# laser_diode_driver.net
KiCad netlist of a schematic drawn in EAGLE
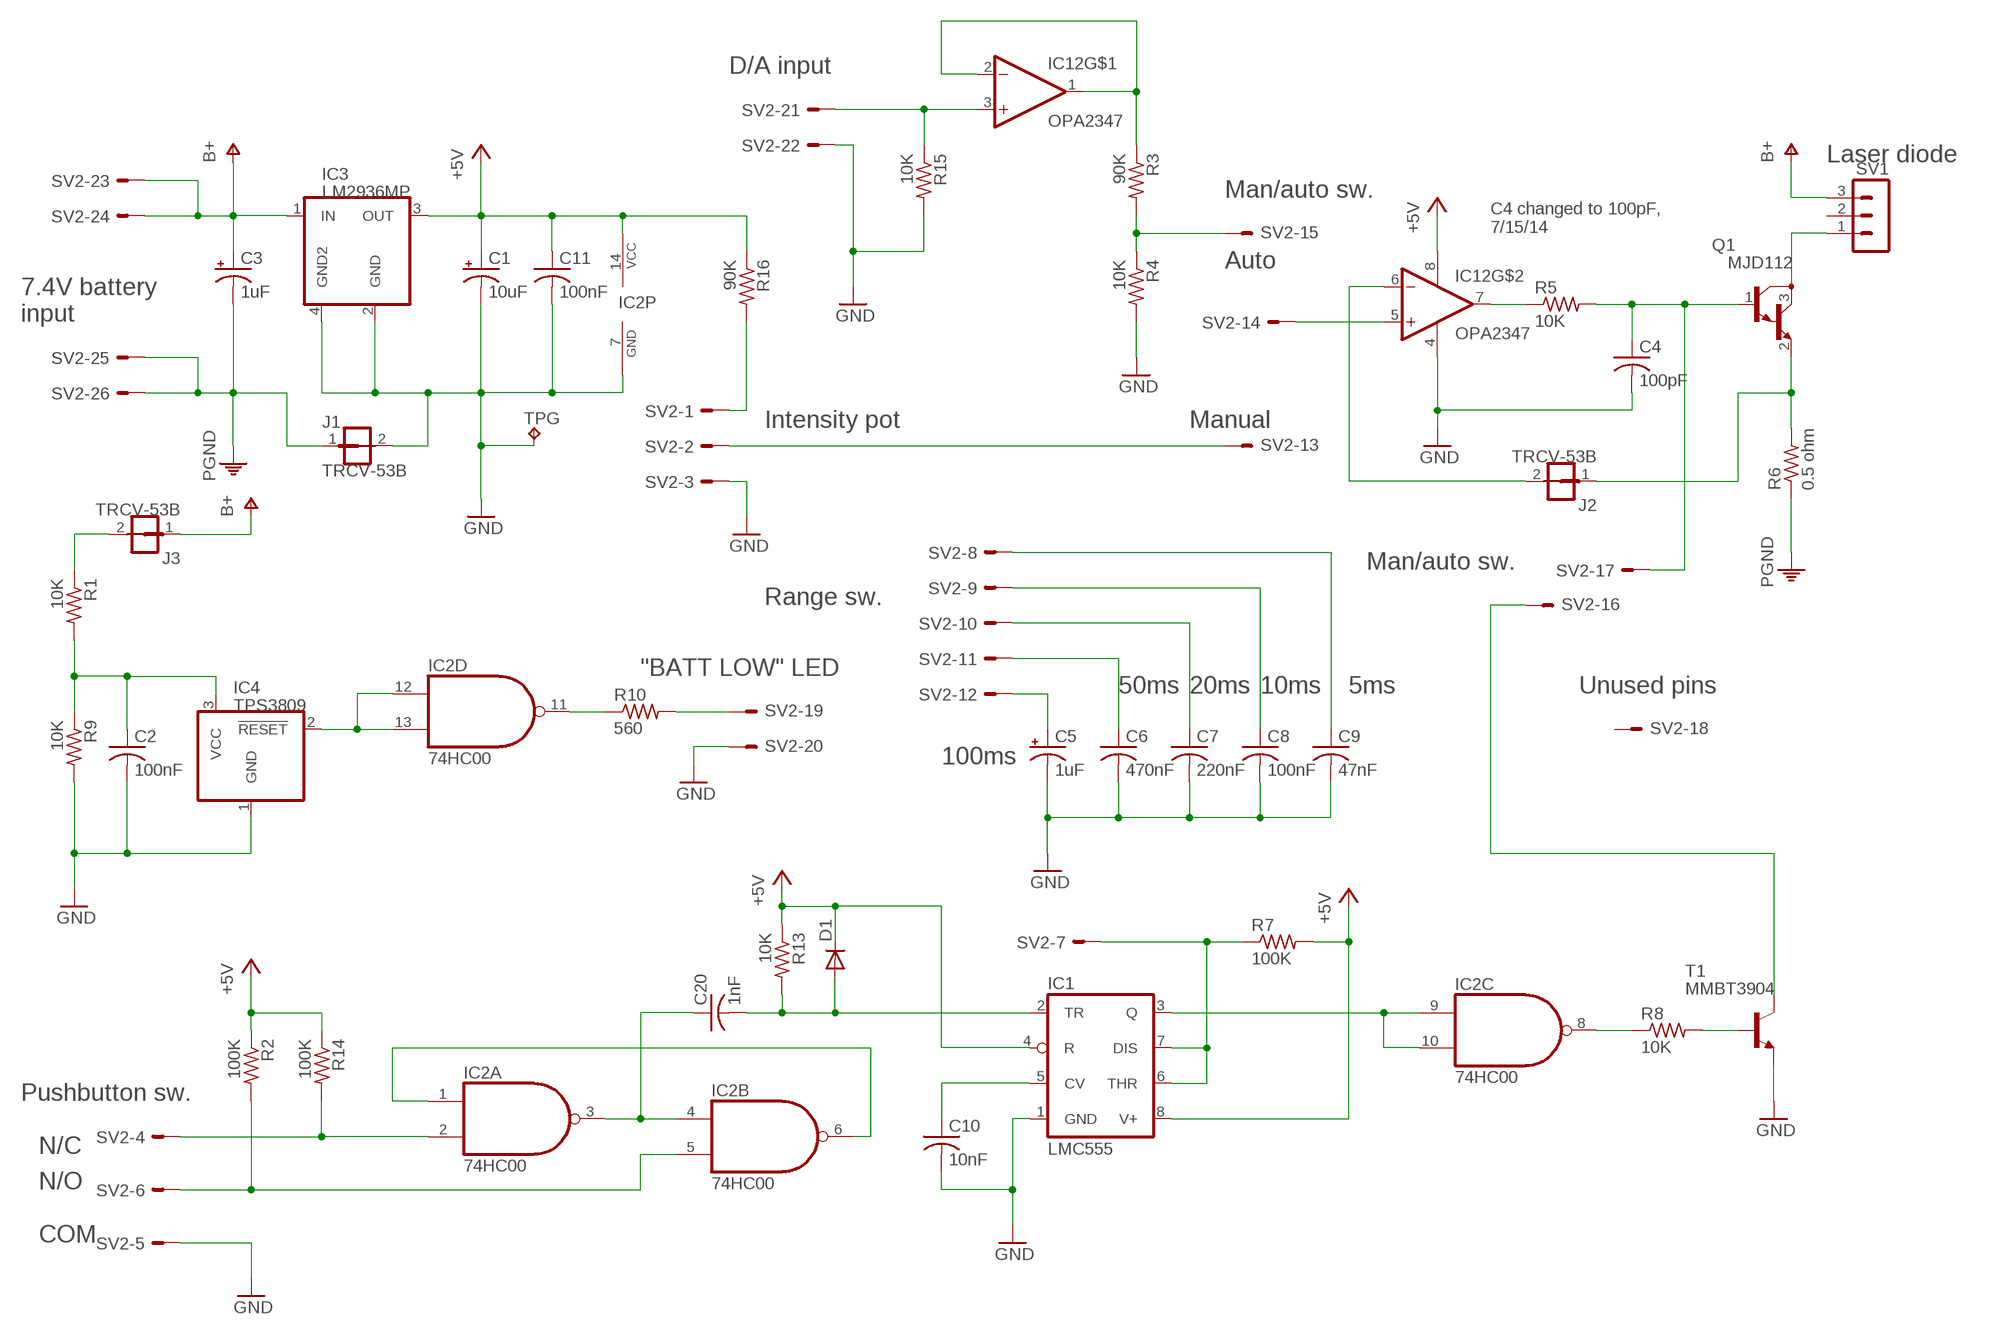
[diagram p0: schematic, sheet 1]

(export (version "E")
  (design (tool "Eeschema 10.0.6"))
  (components
    (comp (ref "C1")
      (value "10uF")
      (footprint "eagle-import:SMC_B")
      (libsource (lib "eagle-import") (part "CPOL-USSMCB"))
    )
    (comp (ref "C2")
      (value "100nF")
      (footprint "eagle-import:C0805")
      (libsource (lib "eagle-import") (part "C-USC0805"))
    )
    (comp (ref "C3")
      (value "1uF")
      (footprint "eagle-import:SMC_B")
      (libsource (lib "eagle-import") (part "CPOL-USSMCB"))
    )
    (comp (ref "C4")
      (value "100pF")
      (footprint "eagle-import:C0805")
      (libsource (lib "eagle-import") (part "C-USC0805"))
    )
    (comp (ref "C5")
      (value "1uF")
      (footprint "eagle-import:SMC_B")
      (libsource (lib "eagle-import") (part "CPOL-USSMCB"))
    )
    (comp (ref "C6")
      (value "470nF")
      (footprint "eagle-import:C0805")
      (libsource (lib "eagle-import") (part "C-USC0805"))
    )
    (comp (ref "C7")
      (value "220nF")
      (footprint "eagle-import:C0805")
      (libsource (lib "eagle-import") (part "C-USC0805"))
    )
    (comp (ref "C8")
      (value "100nF")
      (footprint "eagle-import:C0805")
      (libsource (lib "eagle-import") (part "C-USC0805"))
    )
    (comp (ref "C9")
      (value "47nF")
      (footprint "eagle-import:C0805")
      (libsource (lib "eagle-import") (part "C-USC0805"))
    )
    (comp (ref "C10")
      (value "10nF")
      (footprint "eagle-import:C0805")
      (libsource (lib "eagle-import") (part "C-USC0805"))
    )
    (comp (ref "C11")
      (value "100nF")
      (footprint "eagle-import:C0805")
      (libsource (lib "eagle-import") (part "C-USC0805"))
    )
    (comp (ref "C20")
      (value "1nF")
      (footprint "eagle-import:C0805")
      (libsource (lib "eagle-import") (part "C-USC0805"))
    )
    (comp (ref "D1")
      (value "DIODE-SOD123")
      (footprint "eagle-import:SOD123")
      (libsource (lib "eagle-import") (part "DIODE-SOD123"))
    )
    (comp (ref "IC1")
      (value "LMC555")
      (footprint "eagle-import:SO08")
      (libsource (lib "eagle-import") (part "555DLM"))
    )
    (comp (ref "IC2")
      (value "74HC00")
      (footprint "eagle-import:SO14")
      (libsource (lib "eagle-import") (part "7400DALS"))
    )
    (comp (ref "IC3")
      (value "LM2936MP")
      (footprint "eagle-import:SOT223")
      (libsource (lib "eagle-import") (part "LM2936MP"))
    )
    (comp (ref "IC4")
      (value "TPS3809")
      (footprint "eagle-import:SOT23")
      (libsource (lib "eagle-import") (part "TPS3809"))
    )
    (comp (ref "IC12")
      (value "OPA2347")
      (footprint "eagle-import:SO08")
      (libsource (lib "eagle-import") (part "OPA2227-SO8"))
    )
    (comp (ref "J1")
      (value "TRCV-53B")
      (footprint "eagle-import:JUMPER-TRACE-CONVERT-53-VER2")
      (libsource (lib "eagle-import") (part "TRCV-53B"))
    )
    (comp (ref "J2")
      (value "TRCV-53B")
      (footprint "eagle-import:JUMPER-TRACE-CONVERT-53-VER2")
      (libsource (lib "eagle-import") (part "TRCV-53B"))
    )
    (comp (ref "J3")
      (value "TRCV-53B")
      (footprint "eagle-import:JUMPER-TRACE-CONVERT-53-VER2")
      (libsource (lib "eagle-import") (part "TRCV-53B"))
    )
    (comp (ref "Q1")
      (value "MJD112")
      (footprint "eagle-import:TO252")
      (libsource (lib "eagle-import") (part "MJD112"))
    )
    (comp (ref "R1")
      (value "10K")
      (footprint "eagle-import:R0805")
      (libsource (lib "eagle-import") (part "R-US_R0805"))
    )
    (comp (ref "R2")
      (value "100K")
      (footprint "eagle-import:R0805")
      (libsource (lib "eagle-import") (part "R-US_R0805"))
    )
    (comp (ref "R3")
      (value "90K")
      (footprint "eagle-import:R0805")
      (libsource (lib "eagle-import") (part "R-US_R0805"))
    )
    (comp (ref "R4")
      (value "10K")
      (footprint "eagle-import:R0805")
      (libsource (lib "eagle-import") (part "R-US_R0805"))
    )
    (comp (ref "R5")
      (value "10K")
      (footprint "eagle-import:R0805")
      (libsource (lib "eagle-import") (part "R-US_R0805"))
    )
    (comp (ref "R6")
      (value "0.5 ohm")
      (footprint "eagle-import:R2512")
      (libsource (lib "eagle-import") (part "R-US_R2512"))
    )
    (comp (ref "R7")
      (value "100K")
      (footprint "eagle-import:R0805")
      (libsource (lib "eagle-import") (part "R-US_R0805"))
    )
    (comp (ref "R8")
      (value "10K")
      (footprint "eagle-import:R0805")
      (libsource (lib "eagle-import") (part "R-US_R0805"))
    )
    (comp (ref "R9")
      (value "10K")
      (footprint "eagle-import:R0805")
      (libsource (lib "eagle-import") (part "R-US_R0805"))
    )
    (comp (ref "R10")
      (value "560")
      (footprint "eagle-import:R0805")
      (libsource (lib "eagle-import") (part "R-US_R0805"))
    )
    (comp (ref "R13")
      (value "10K")
      (footprint "eagle-import:R0805")
      (libsource (lib "eagle-import") (part "R-US_R0805"))
    )
    (comp (ref "R14")
      (value "100K")
      (footprint "eagle-import:R0805")
      (libsource (lib "eagle-import") (part "R-US_R0805"))
    )
    (comp (ref "R15")
      (value "10K")
      (footprint "eagle-import:R0805")
      (libsource (lib "eagle-import") (part "R-US_R0805"))
    )
    (comp (ref "R16")
      (value "90K")
      (footprint "eagle-import:R0805")
      (libsource (lib "eagle-import") (part "R-US_R0805"))
    )
    (comp (ref "SV1")
      (value "MA03-1")
      (footprint "eagle-import:MA03-1")
      (libsource (lib "eagle-import") (part "MA03-1"))
    )
    (comp (ref "SV2")
      (value "ML26LE")
      (footprint "eagle-import:ML26L")
      (libsource (lib "eagle-import") (part "ML26?EL"))
    )
    (comp (ref "T1")
      (value "MMBT3904")
      (footprint "eagle-import:SOT23-BEC")
      (libsource (lib "eagle-import") (part "-NPN-SOT23-BECMMBT3904LT1"))
    )
    (comp (ref "TPG")
      (value "TP-040-100")
      (footprint "eagle-import:P1-040-100")
      (libsource (lib "eagle-import") (part "TP-040-100"))
    )
  )
  (nets
    (net (code "1") (name "+5V") (class "Default")
      (node (ref "C1") (pin "+") (pinfunction "+_+") (pintype "passive"))
      (node (ref "C11") (pin "1") (pinfunction "1_1") (pintype "passive"))
      (node (ref "D1") (pin "C") (pinfunction "C_C") (pintype "passive"))
      (node (ref "IC1") (pin "4") (pinfunction "R_4") (pintype "input"))
      (node (ref "IC1") (pin "8") (pinfunction "V+_8") (pintype "power_in"))
      (node (ref "IC12") (pin "8") (pinfunction "PWR+_8") (pintype "passive"))
      (node (ref "IC2") (pin "14") (pinfunction "VCC_14") (pintype "power_in"))
      (node (ref "IC3") (pin "3") (pinfunction "OUT_3") (pintype "passive"))
      (node (ref "R13") (pin "1") (pinfunction "1_1") (pintype "passive"))
      (node (ref "R14") (pin "1") (pinfunction "1_1") (pintype "passive"))
      (node (ref "R16") (pin "1") (pinfunction "1_1") (pintype "passive"))
      (node (ref "R2") (pin "1") (pinfunction "1_1") (pintype "passive"))
      (node (ref "R7") (pin "2") (pinfunction "2_2") (pintype "passive"))
    )
    (net (code "2") (name "B+") (class "Default")
      (node (ref "C3") (pin "+") (pinfunction "+_+") (pintype "passive"))
      (node (ref "IC3") (pin "1") (pinfunction "IN_1") (pintype "input"))
      (node (ref "J3") (pin "1") (pinfunction "1_1") (pintype "passive"))
      (node (ref "SV1") (pin "3") (pinfunction "3_3") (pintype "passive"))
      (node (ref "SV2") (pin "23") (pinfunction "S_23") (pintype "passive"))
      (node (ref "SV2") (pin "24") (pinfunction "S_24") (pintype "passive"))
    )
    (net (code "3") (name "GND") (class "Default")
      (node (ref "C1") (pin "-") (pinfunction "-_-") (pintype "passive"))
      (node (ref "C10") (pin "2") (pinfunction "2_2") (pintype "passive"))
      (node (ref "C11") (pin "2") (pinfunction "2_2") (pintype "passive"))
      (node (ref "C2") (pin "2") (pinfunction "2_2") (pintype "passive"))
      (node (ref "C4") (pin "2") (pinfunction "2_2") (pintype "passive"))
      (node (ref "C5") (pin "-") (pinfunction "-_-") (pintype "passive"))
      (node (ref "C6") (pin "2") (pinfunction "2_2") (pintype "passive"))
      (node (ref "C7") (pin "2") (pinfunction "2_2") (pintype "passive"))
      (node (ref "C8") (pin "2") (pinfunction "2_2") (pintype "passive"))
      (node (ref "C9") (pin "2") (pinfunction "2_2") (pintype "passive"))
      (node (ref "IC1") (pin "1") (pinfunction "GND_1") (pintype "power_in"))
      (node (ref "IC12") (pin "4") (pinfunction "PWR-_4") (pintype "passive"))
      (node (ref "IC2") (pin "7") (pinfunction "GND_7") (pintype "power_in"))
      (node (ref "IC3") (pin "2") (pinfunction "GND_2") (pintype "passive"))
      (node (ref "IC3") (pin "4") (pinfunction "GND2_4") (pintype "passive"))
      (node (ref "IC4") (pin "1") (pinfunction "GND_1") (pintype "passive"))
      (node (ref "J1") (pin "2") (pinfunction "2_2") (pintype "passive"))
      (node (ref "R15") (pin "2") (pinfunction "2_2") (pintype "passive"))
      (node (ref "R4") (pin "2") (pinfunction "2_2") (pintype "passive"))
      (node (ref "R9") (pin "2") (pinfunction "2_2") (pintype "passive"))
      (node (ref "SV2") (pin "20") (pinfunction "S_20") (pintype "passive"))
      (node (ref "SV2") (pin "22") (pinfunction "S_22") (pintype "passive"))
      (node (ref "SV2") (pin "3") (pinfunction "S_3") (pintype "passive"))
      (node (ref "SV2") (pin "5") (pinfunction "S_5") (pintype "passive"))
      (node (ref "T1") (pin "E") (pinfunction "E_E") (pintype "passive"))
      (node (ref "TPG") (pin "P$1") (pinfunction "TP_P$1") (pintype "passive"))
    )
    (net (code "4") (name "Net-(IC1-CV)") (class "Default")
      (node (ref "C10") (pin "1") (pinfunction "1_1") (pintype "passive"))
      (node (ref "IC1") (pin "5") (pinfunction "CV_5") (pintype "input"))
    )
    (net (code "5") (name "Net-(IC1-DIS)") (class "Default")
      (node (ref "IC1") (pin "6") (pinfunction "THR_6") (pintype "input"))
      (node (ref "IC1") (pin "7") (pinfunction "DIS_7") (pintype "input"))
      (node (ref "R7") (pin "1") (pinfunction "1_1") (pintype "passive"))
      (node (ref "SV2") (pin "7") (pinfunction "S_7") (pintype "passive"))
    )
    (net (code "6") (name "Net-(IC1-Q)") (class "Default")
      (node (ref "IC1") (pin "3") (pinfunction "Q_3") (pintype "output"))
      (node (ref "IC2") (pin "10") (pinfunction "I1_10") (pintype "input"))
      (node (ref "IC2") (pin "9") (pinfunction "I0_9") (pintype "input"))
    )
    (net (code "7") (name "Net-(IC1-TR)") (class "Default")
      (node (ref "C20") (pin "2") (pinfunction "2_2") (pintype "passive"))
      (node (ref "D1") (pin "A") (pinfunction "A_A") (pintype "passive"))
      (node (ref "IC1") (pin "2") (pinfunction "TR_2") (pintype "input"))
      (node (ref "R13") (pin "2") (pinfunction "2_2") (pintype "passive"))
    )
    (net (code "8") (name "Net-(IC2A-I0)") (class "Default")
      (node (ref "IC2") (pin "1") (pinfunction "I0_1") (pintype "input"))
      (node (ref "IC2") (pin "6") (pinfunction "O_6") (pintype "output"))
    )
    (net (code "9") (name "Net-(IC2A-I1)") (class "Default")
      (node (ref "IC2") (pin "2") (pinfunction "I1_2") (pintype "input"))
      (node (ref "R14") (pin "2") (pinfunction "2_2") (pintype "passive"))
      (node (ref "SV2") (pin "4") (pinfunction "S_4") (pintype "passive"))
    )
    (net (code "10") (name "Net-(IC2A-O)") (class "Default")
      (node (ref "C20") (pin "1") (pinfunction "1_1") (pintype "passive"))
      (node (ref "IC2") (pin "3") (pinfunction "O_3") (pintype "output"))
      (node (ref "IC2") (pin "4") (pinfunction "I0_4") (pintype "input"))
    )
    (net (code "11") (name "Net-(IC2B-I1)") (class "Default")
      (node (ref "IC2") (pin "5") (pinfunction "I1_5") (pintype "input"))
      (node (ref "R2") (pin "2") (pinfunction "2_2") (pintype "passive"))
      (node (ref "SV2") (pin "6") (pinfunction "S_6") (pintype "passive"))
    )
    (net (code "12") (name "Net-(IC2C-O)") (class "Default")
      (node (ref "IC2") (pin "8") (pinfunction "O_8") (pintype "output"))
      (node (ref "R8") (pin "1") (pinfunction "1_1") (pintype "passive"))
    )
    (net (code "13") (name "Net-(IC2D-I0)") (class "Default")
      (node (ref "IC2") (pin "12") (pinfunction "I0_12") (pintype "input"))
      (node (ref "IC2") (pin "13") (pinfunction "I1_13") (pintype "input"))
      (node (ref "IC4") (pin "2") (pinfunction "~{RESET}_2") (pintype "passive"))
    )
    (net (code "14") (name "Net-(IC2D-O)") (class "Default")
      (node (ref "IC2") (pin "11") (pinfunction "O_11") (pintype "output"))
      (node (ref "R10") (pin "1") (pinfunction "1_1") (pintype "passive"))
    )
    (net (code "15") (name "Net-(IC4-VCC)") (class "Default")
      (node (ref "C2") (pin "1") (pinfunction "1_1") (pintype "passive"))
      (node (ref "IC4") (pin "3") (pinfunction "VCC_3") (pintype "passive"))
      (node (ref "R1") (pin "2") (pinfunction "2_2") (pintype "passive"))
      (node (ref "R9") (pin "1") (pinfunction "1_1") (pintype "passive"))
    )
    (net (code "16") (name "Net-(IC12A-+IN)") (class "Default")
      (node (ref "IC12") (pin "3") (pinfunction "+IN_3") (pintype "input"))
      (node (ref "R15") (pin "1") (pinfunction "1_1") (pintype "passive"))
      (node (ref "SV2") (pin "21") (pinfunction "S_21") (pintype "passive"))
    )
    (net (code "17") (name "Net-(IC12A--IN)") (class "Default")
      (node (ref "IC12") (pin "1") (pinfunction "OUT_1") (pintype "output"))
      (node (ref "IC12") (pin "2") (pinfunction "-IN_2") (pintype "input"))
      (node (ref "R3") (pin "1") (pinfunction "1_1") (pintype "passive"))
    )
    (net (code "18") (name "Net-(IC12B-+IN)") (class "Default")
      (node (ref "IC12") (pin "5") (pinfunction "+IN_5") (pintype "input"))
      (node (ref "SV2") (pin "14") (pinfunction "S_14") (pintype "passive"))
    )
    (net (code "19") (name "Net-(IC12B--IN)") (class "Default")
      (node (ref "IC12") (pin "6") (pinfunction "-IN_6") (pintype "input"))
      (node (ref "J2") (pin "2") (pinfunction "2_2") (pintype "passive"))
    )
    (net (code "20") (name "Net-(IC12B-OUT)") (class "Default")
      (node (ref "IC12") (pin "7") (pinfunction "OUT_7") (pintype "output"))
      (node (ref "R5") (pin "1") (pinfunction "1_1") (pintype "passive"))
    )
    (net (code "21") (name "Net-(J3-Pad2)") (class "Default")
      (node (ref "J3") (pin "2") (pinfunction "2_2") (pintype "passive"))
      (node (ref "R1") (pin "1") (pinfunction "1_1") (pintype "passive"))
    )
    (net (code "22") (name "Net-(Q1-B)") (class "Default")
      (node (ref "C4") (pin "1") (pinfunction "1_1") (pintype "passive"))
      (node (ref "Q1") (pin "1") (pinfunction "B_1") (pintype "passive"))
      (node (ref "R5") (pin "2") (pinfunction "2_2") (pintype "passive"))
      (node (ref "SV2") (pin "17") (pinfunction "S_17") (pintype "passive"))
    )
    (net (code "23") (name "Net-(Q1-C)") (class "Default")
      (node (ref "Q1") (pin "3") (pinfunction "C_3") (pintype "passive"))
      (node (ref "SV1") (pin "1") (pinfunction "1_1") (pintype "passive"))
    )
    (net (code "24") (name "Net-(Q1-E)") (class "Default")
      (node (ref "J2") (pin "1") (pinfunction "1_1") (pintype "passive"))
      (node (ref "Q1") (pin "2") (pinfunction "E_2") (pintype "passive"))
      (node (ref "R6") (pin "2") (pinfunction "2_2") (pintype "passive"))
    )
    (net (code "25") (name "Net-(R8-Pad2)") (class "Default")
      (node (ref "R8") (pin "2") (pinfunction "2_2") (pintype "passive"))
      (node (ref "T1") (pin "B") (pinfunction "B_B") (pintype "passive"))
    )
    (net (code "26") (name "Net-(SV2A-S)") (class "Default")
      (node (ref "R16") (pin "2") (pinfunction "2_2") (pintype "passive"))
      (node (ref "SV2") (pin "1") (pinfunction "S_1") (pintype "passive"))
    )
    (net (code "27") (name "Net-(SV2B-S)") (class "Default")
      (node (ref "C7") (pin "1") (pinfunction "1_1") (pintype "passive"))
      (node (ref "SV2") (pin "10") (pinfunction "S_10") (pintype "passive"))
    )
    (net (code "28") (name "Net-(SV2C-S)") (class "Default")
      (node (ref "C6") (pin "1") (pinfunction "1_1") (pintype "passive"))
      (node (ref "SV2") (pin "11") (pinfunction "S_11") (pintype "passive"))
    )
    (net (code "29") (name "Net-(SV2D-S)") (class "Default")
      (node (ref "C5") (pin "+") (pinfunction "+_+") (pintype "passive"))
      (node (ref "SV2") (pin "12") (pinfunction "S_12") (pintype "passive"))
    )
    (net (code "30") (name "Net-(SV2E-S)") (class "Default")
      (node (ref "SV2") (pin "13") (pinfunction "S_13") (pintype "passive"))
      (node (ref "SV2") (pin "2") (pinfunction "S_2") (pintype "passive"))
    )
    (net (code "31") (name "Net-(SV2G-S)") (class "Default")
      (node (ref "R3") (pin "2") (pinfunction "2_2") (pintype "passive"))
      (node (ref "R4") (pin "1") (pinfunction "1_1") (pintype "passive"))
      (node (ref "SV2") (pin "15") (pinfunction "S_15") (pintype "passive"))
    )
    (net (code "32") (name "Net-(SV2H-S)") (class "Default")
      (node (ref "SV2") (pin "16") (pinfunction "S_16") (pintype "passive"))
      (node (ref "T1") (pin "C") (pinfunction "C_C") (pintype "passive"))
    )
    (net (code "33") (name "Net-(SV2K-S)") (class "Default")
      (node (ref "R10") (pin "2") (pinfunction "2_2") (pintype "passive"))
      (node (ref "SV2") (pin "19") (pinfunction "S_19") (pintype "passive"))
    )
    (net (code "34") (name "Net-(SV2Y-S)") (class "Default")
      (node (ref "C9") (pin "1") (pinfunction "1_1") (pintype "passive"))
      (node (ref "SV2") (pin "8") (pinfunction "S_8") (pintype "passive"))
    )
    (net (code "35") (name "Net-(SV2Z-S)") (class "Default")
      (node (ref "C8") (pin "1") (pinfunction "1_1") (pintype "passive"))
      (node (ref "SV2") (pin "9") (pinfunction "S_9") (pintype "passive"))
    )
    (net (code "36") (name "PGND") (class "Default")
      (node (ref "C3") (pin "-") (pinfunction "-_-") (pintype "passive"))
      (node (ref "J1") (pin "1") (pinfunction "1_1") (pintype "passive"))
      (node (ref "R6") (pin "1") (pinfunction "1_1") (pintype "passive"))
      (node (ref "SV2") (pin "25") (pinfunction "S_25") (pintype "passive"))
      (node (ref "SV2") (pin "26") (pinfunction "S_26") (pintype "passive"))
    )
    (net (code "37") (name "unconnected-(SV1-Pad2)") (class "Default")
      (node (ref "SV1") (pin "2") (pinfunction "2_2") (pintype "passive"))
    )
    (net (code "38") (name "unconnected-(SV2J-S-Pad18)") (class "Default")
      (node (ref "SV2") (pin "18") (pinfunction "S_18") (pintype "passive"))
    )
  )
)
